# Ai_Cricket.net
KiCad netlist of a schematic drawn in EAGLE
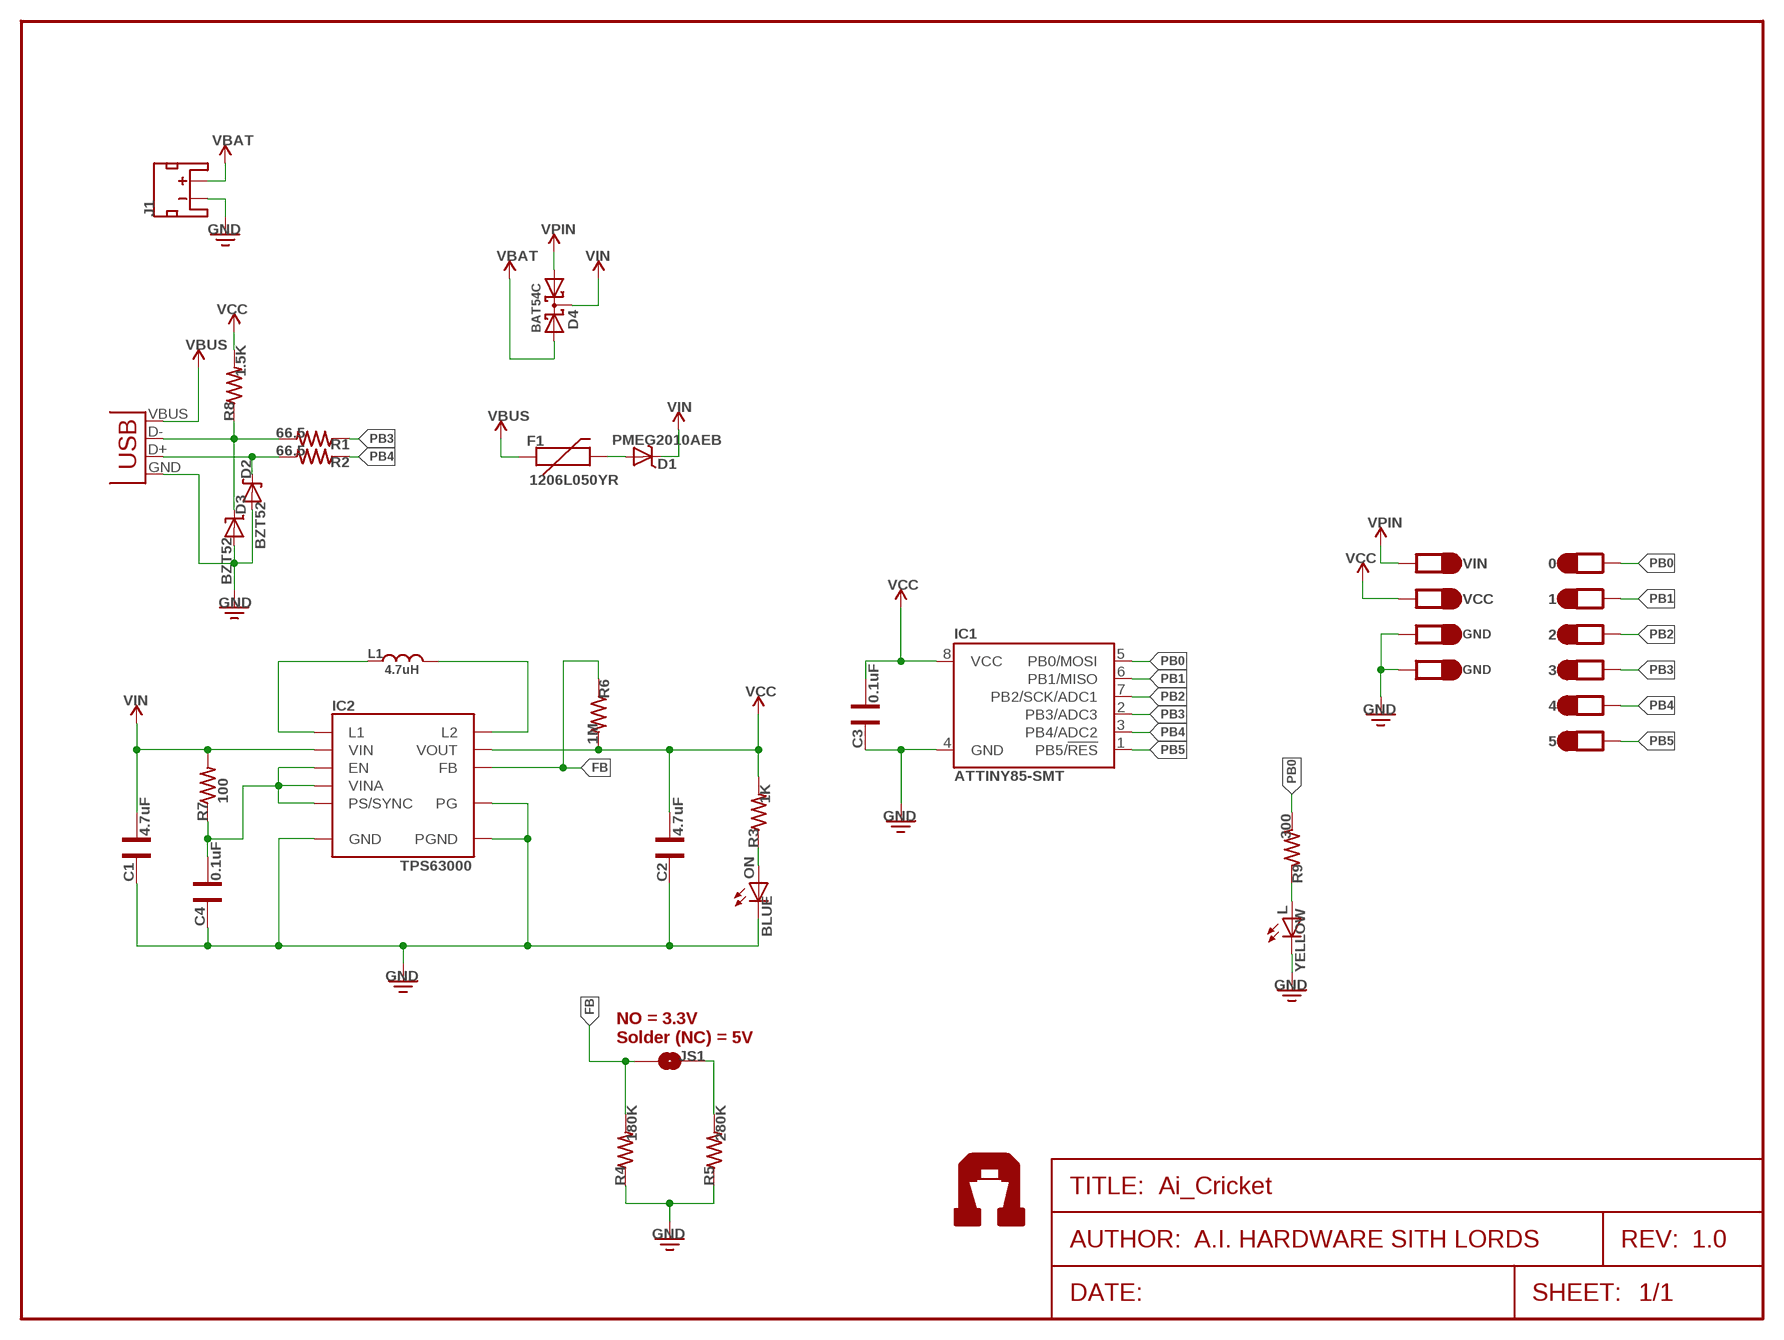
[diagram p0: schematic, sheet 1]

(export (version "E")
  (design (tool "Eeschema 10.0.6"))
  (components
    (comp (ref "0")
      (value "1X01-PETAL")
      (footprint "eagle-import:1X01-PETAL")
      (libsource (lib "eagle-import") (part "1X01-PETAL"))
    )
    (comp (ref "1")
      (value "1X01-PETAL")
      (footprint "eagle-import:1X01-PETAL")
      (libsource (lib "eagle-import") (part "1X01-PETAL"))
    )
    (comp (ref "2")
      (value "1X01-PETAL")
      (footprint "eagle-import:1X01-PETAL")
      (libsource (lib "eagle-import") (part "1X01-PETAL"))
    )
    (comp (ref "3")
      (value "1X01-PETAL")
      (footprint "eagle-import:1X01-PETAL")
      (libsource (lib "eagle-import") (part "1X01-PETAL"))
    )
    (comp (ref "4")
      (value "1X01-PETAL")
      (footprint "eagle-import:1X01-PETAL")
      (libsource (lib "eagle-import") (part "1X01-PETAL"))
    )
    (comp (ref "5")
      (value "1X01-PETAL")
      (footprint "eagle-import:1X01-PETAL")
      (libsource (lib "eagle-import") (part "1X01-PETAL"))
    )
    (comp (ref "C1")
      (value "4.7uF")
      (footprint "eagle-import:CAP-0402")
      (libsource (lib "eagle-import") (part "CAP0402"))
    )
    (comp (ref "C2")
      (value "4.7uF")
      (footprint "eagle-import:CAP-0402")
      (libsource (lib "eagle-import") (part "CAP0402"))
    )
    (comp (ref "C3")
      (value "0.1uF")
      (footprint "eagle-import:CAP-0402")
      (libsource (lib "eagle-import") (part "CAP0402"))
    )
    (comp (ref "C4")
      (value "0.1uF")
      (footprint "eagle-import:CAP-0402")
      (libsource (lib "eagle-import") (part "CAP0402"))
    )
    (comp (ref "D1")
      (value "PMEG2010AEB")
      (footprint "eagle-import:SOD-523")
      (libsource (lib "eagle-import") (part "DIODE-SCHOTTKYSOD-523"))
    )
    (comp (ref "D2")
      (value "BZT52")
      (footprint "eagle-import:SOD-323")
      (libsource (lib "eagle-import") (part "DIODE-ZENER-BZT52"))
    )
    (comp (ref "D3")
      (value "BZT52")
      (footprint "eagle-import:SOD-323")
      (libsource (lib "eagle-import") (part "DIODE-ZENER-BZT52"))
    )
    (comp (ref "D4")
      (value "BAT54C")
      (footprint "eagle-import:SOT-23")
      (libsource (lib "eagle-import") (part "BAT54C"))
    )
    (comp (ref "F1")
      (value "1206L050YR")
      (footprint "eagle-import:PTC-1206")
      (libsource (lib "eagle-import") (part "PTCSMD"))
    )
    (comp (ref "GND7")
      (value "1X01-PETAL")
      (footprint "eagle-import:1X01-PETAL")
      (libsource (lib "eagle-import") (part "1X01-PETAL"))
    )
    (comp (ref "GND8")
      (value "1X01-PETAL")
      (footprint "eagle-import:1X01-PETAL")
      (libsource (lib "eagle-import") (part "1X01-PETAL"))
    )
    (comp (ref "IC1")
      (value "ATTINY85-SMT")
      (footprint "eagle-import:S008-EIAJ")
      (libsource (lib "eagle-import") (part "ATTINY85-SMT"))
    )
    (comp (ref "IC2")
      (value "TPS63000")
      (footprint "eagle-import:10-VFDFN")
      (libsource (lib "eagle-import") (part "TPS63000"))
    )
    (comp (ref "J1")
      (value "JST-2-MALE")
      (footprint "eagle-import:JST-2-SMD")
      (libsource (lib "eagle-import") (part "JST-2-MALE"))
    )
    (comp (ref "JS1")
      (value "1X02-SJ-NO")
      (footprint "eagle-import:1X02-SJ-NO")
      (libsource (lib "eagle-import") (part "1X02-SJ-NO"))
    )
    (comp (ref "L")
      (value "YELLOW")
      (footprint "eagle-import:LED-0603")
      (libsource (lib "eagle-import") (part "LED0603"))
    )
    (comp (ref "L1")
      (value "4.7uH")
      (footprint "eagle-import:IND-0603")
      (libsource (lib "eagle-import") (part "IND0603"))
    )
    (comp (ref "ON")
      (value "BLUE")
      (footprint "eagle-import:LED-0603")
      (libsource (lib "eagle-import") (part "LED0603"))
    )
    (comp (ref "R1")
      (value "66.5")
      (footprint "eagle-import:RES-0402")
      (libsource (lib "eagle-import") (part "RES0402"))
    )
    (comp (ref "R2")
      (value "66.5")
      (footprint "eagle-import:RES-0402")
      (libsource (lib "eagle-import") (part "RES0402"))
    )
    (comp (ref "R3")
      (value "1K")
      (footprint "eagle-import:RES-0402")
      (libsource (lib "eagle-import") (part "RES0402"))
    )
    (comp (ref "R4")
      (value "180K")
      (footprint "eagle-import:RES-0402")
      (libsource (lib "eagle-import") (part "RES0402"))
    )
    (comp (ref "R5")
      (value "280K")
      (footprint "eagle-import:RES-0402")
      (libsource (lib "eagle-import") (part "RES0402"))
    )
    (comp (ref "R6")
      (value "1M")
      (footprint "eagle-import:RES-0402")
      (libsource (lib "eagle-import") (part "RES0402"))
    )
    (comp (ref "R7")
      (value "100")
      (footprint "eagle-import:RES-0402")
      (libsource (lib "eagle-import") (part "RES0402"))
    )
    (comp (ref "R8")
      (value "1.5K")
      (footprint "eagle-import:RES-0402")
      (libsource (lib "eagle-import") (part "RES0402"))
    )
    (comp (ref "R9")
      (value "300")
      (footprint "eagle-import:RES-0402")
      (libsource (lib "eagle-import") (part "RES0402"))
    )
    (comp (ref "U$14")
      (value "AI-LOGOXS")
      (footprint "eagle-import:AI-LOGO-XS")
      (libsource (lib "eagle-import") (part "AI-LOGOXS"))
    )
    (comp (ref "USB1")
      (value "USBMICROB-TH")
      (footprint "eagle-import:USB-MICROB-TH")
      (libsource (lib "eagle-import") (part "USBMICROB-TH"))
    )
    (comp (ref "VCC")
      (value "1X01-PETAL")
      (footprint "eagle-import:1X01-PETAL")
      (libsource (lib "eagle-import") (part "1X01-PETAL"))
    )
    (comp (ref "VIN")
      (value "1X01-PETAL")
      (footprint "eagle-import:1X01-PETAL")
      (libsource (lib "eagle-import") (part "1X01-PETAL"))
    )
  )
  (nets
    (net (code "1") (name "FB") (class "Default")
      (node (ref "IC2") (pin "10") (pinfunction "FB_10") (pintype "input"))
      (node (ref "JS1") (pin "1") (pinfunction "1_1") (pintype "passive"))
      (node (ref "R4") (pin "2") (pinfunction "2_2") (pintype "passive"))
      (node (ref "R6") (pin "1") (pinfunction "1_1") (pintype "passive"))
    )
    (net (code "2") (name "GND") (class "Default")
      (node (ref "C1") (pin "2") (pinfunction "2_2") (pintype "passive"))
      (node (ref "C2") (pin "2") (pinfunction "2_2") (pintype "passive"))
      (node (ref "C3") (pin "2") (pinfunction "2_2") (pintype "passive"))
      (node (ref "C4") (pin "2") (pinfunction "2_2") (pintype "passive"))
      (node (ref "D2") (pin "A") (pinfunction "A_A") (pintype "passive"))
      (node (ref "D3") (pin "A") (pinfunction "A_A") (pintype "passive"))
      (node (ref "GND7") (pin "1") (pinfunction "1_1") (pintype "bidirectional"))
      (node (ref "GND8") (pin "1") (pinfunction "1_1") (pintype "bidirectional"))
      (node (ref "IC1") (pin "4") (pinfunction "GND_4") (pintype "bidirectional"))
      (node (ref "IC2") (pin "3") (pinfunction "PGND_3") (pintype "power_in"))
      (node (ref "IC2") (pin "9") (pinfunction "GND_9") (pintype "power_in"))
      (node (ref "IC2") (pin "P$1") (pinfunction "PG_P$1") (pintype "power_in"))
      (node (ref "IC2") (pin "P$2") (pinfunction "PG_P$2") (pintype "power_in"))
      (node (ref "IC2") (pin "P$3") (pinfunction "PG_P$3") (pintype "power_in"))
      (node (ref "IC2") (pin "P$4") (pinfunction "PG_P$4") (pintype "power_in"))
      (node (ref "IC2") (pin "P$5") (pinfunction "PG_P$5") (pintype "power_in"))
      (node (ref "J1") (pin "2") (pinfunction "-_2") (pintype "power_in"))
      (node (ref "L") (pin "C") (pinfunction "C_C") (pintype "passive"))
      (node (ref "ON") (pin "C") (pinfunction "C_C") (pintype "passive"))
      (node (ref "R4") (pin "1") (pinfunction "1_1") (pintype "passive"))
      (node (ref "R5") (pin "1") (pinfunction "1_1") (pintype "passive"))
      (node (ref "USB1") (pin "GND") (pinfunction "GND_GND") (pintype "bidirectional"))
    )
    (net (code "3") (name "Net-(D1-PadA)") (class "Default")
      (node (ref "D1") (pin "A") (pinfunction "A_A") (pintype "passive"))
      (node (ref "F1") (pin "2") (pinfunction "2_2") (pintype "bidirectional"))
    )
    (net (code "4") (name "Net-(D2-PadC)") (class "Default")
      (node (ref "D2") (pin "C") (pinfunction "C_C") (pintype "passive"))
      (node (ref "R2") (pin "2") (pinfunction "2_2") (pintype "passive"))
      (node (ref "USB1") (pin "D+") (pinfunction "D+_D+") (pintype "bidirectional"))
    )
    (net (code "5") (name "Net-(D3-PadC)") (class "Default")
      (node (ref "D3") (pin "C") (pinfunction "C_C") (pintype "passive"))
      (node (ref "R1") (pin "2") (pinfunction "2_2") (pintype "passive"))
      (node (ref "R8") (pin "1") (pinfunction "1_1") (pintype "passive"))
      (node (ref "USB1") (pin "D-") (pinfunction "D-_D-") (pintype "bidirectional"))
    )
    (net (code "6") (name "Net-(IC2-EN)") (class "Default")
      (node (ref "C4") (pin "1") (pinfunction "1_1") (pintype "passive"))
      (node (ref "IC2") (pin "6") (pinfunction "EN_6") (pintype "bidirectional"))
      (node (ref "IC2") (pin "7") (pinfunction "PS/SYNC_7") (pintype "input"))
      (node (ref "IC2") (pin "8") (pinfunction "VINA_8") (pintype "power_in"))
      (node (ref "R7") (pin "1") (pinfunction "1_1") (pintype "passive"))
    )
    (net (code "7") (name "Net-(IC2-L1)") (class "Default")
      (node (ref "IC2") (pin "4") (pinfunction "L1_4") (pintype "passive"))
      (node (ref "L1") (pin "2") (pinfunction "2_2") (pintype "passive"))
    )
    (net (code "8") (name "Net-(IC2-L2)") (class "Default")
      (node (ref "IC2") (pin "2") (pinfunction "L2_2") (pintype "passive"))
      (node (ref "L1") (pin "1") (pinfunction "1_1") (pintype "passive"))
    )
    (net (code "9") (name "Net-(JS1-Pad2)") (class "Default")
      (node (ref "JS1") (pin "2") (pinfunction "2_2") (pintype "passive"))
      (node (ref "R5") (pin "2") (pinfunction "2_2") (pintype "passive"))
    )
    (net (code "10") (name "Net-(L-PadA)") (class "Default")
      (node (ref "L") (pin "A") (pinfunction "A_A") (pintype "passive"))
      (node (ref "R9") (pin "1") (pinfunction "1_1") (pintype "passive"))
    )
    (net (code "11") (name "Net-(ON-PadA)") (class "Default")
      (node (ref "ON") (pin "A") (pinfunction "A_A") (pintype "passive"))
      (node (ref "R3") (pin "1") (pinfunction "1_1") (pintype "passive"))
    )
    (net (code "12") (name "PB0") (class "Default")
      (node (ref "0") (pin "1") (pinfunction "1_1") (pintype "bidirectional"))
      (node (ref "IC1") (pin "5") (pinfunction "PB0/MOSI_5") (pintype "bidirectional"))
      (node (ref "R9") (pin "2") (pinfunction "2_2") (pintype "passive"))
    )
    (net (code "13") (name "PB1") (class "Default")
      (node (ref "1") (pin "1") (pinfunction "1_1") (pintype "bidirectional"))
      (node (ref "IC1") (pin "6") (pinfunction "PB1/MISO_6") (pintype "bidirectional"))
    )
    (net (code "14") (name "PB2") (class "Default")
      (node (ref "2") (pin "1") (pinfunction "1_1") (pintype "bidirectional"))
      (node (ref "IC1") (pin "7") (pinfunction "PB2/SCK/ADC1_7") (pintype "bidirectional"))
    )
    (net (code "15") (name "PB3") (class "Default")
      (node (ref "3") (pin "1") (pinfunction "1_1") (pintype "bidirectional"))
      (node (ref "IC1") (pin "2") (pinfunction "PB3/ADC3_2") (pintype "bidirectional"))
      (node (ref "R1") (pin "1") (pinfunction "1_1") (pintype "passive"))
    )
    (net (code "16") (name "PB4") (class "Default")
      (node (ref "4") (pin "1") (pinfunction "1_1") (pintype "bidirectional"))
      (node (ref "IC1") (pin "3") (pinfunction "PB4/ADC2_3") (pintype "bidirectional"))
      (node (ref "R2") (pin "1") (pinfunction "1_1") (pintype "passive"))
    )
    (net (code "17") (name "PB5") (class "Default")
      (node (ref "5") (pin "1") (pinfunction "1_1") (pintype "bidirectional"))
      (node (ref "IC1") (pin "1") (pinfunction "PB5/~{RES}_1") (pintype "bidirectional"))
    )
    (net (code "18") (name "VBAT") (class "Default")
      (node (ref "D4") (pin "2") (pinfunction "A2_2") (pintype "passive"))
      (node (ref "J1") (pin "1") (pinfunction "+_1") (pintype "power_in"))
    )
    (net (code "19") (name "VBUS") (class "Default")
      (node (ref "F1") (pin "1") (pinfunction "1_1") (pintype "bidirectional"))
      (node (ref "USB1") (pin "VBUS") (pinfunction "VBUS_VBUS") (pintype "bidirectional"))
    )
    (net (code "20") (name "VCC") (class "Default")
      (node (ref "C2") (pin "1") (pinfunction "1_1") (pintype "passive"))
      (node (ref "C3") (pin "1") (pinfunction "1_1") (pintype "passive"))
      (node (ref "IC1") (pin "8") (pinfunction "VCC_8") (pintype "bidirectional"))
      (node (ref "IC2") (pin "1") (pinfunction "VOUT_1") (pintype "power_in"))
      (node (ref "R3") (pin "2") (pinfunction "2_2") (pintype "passive"))
      (node (ref "R6") (pin "2") (pinfunction "2_2") (pintype "passive"))
      (node (ref "R8") (pin "2") (pinfunction "2_2") (pintype "passive"))
      (node (ref "VCC") (pin "1") (pinfunction "1_1") (pintype "bidirectional"))
    )
    (net (code "21") (name "VIN") (class "Default")
      (node (ref "C1") (pin "1") (pinfunction "1_1") (pintype "passive"))
      (node (ref "D1") (pin "C") (pinfunction "C_C") (pintype "passive"))
      (node (ref "D4") (pin "3") (pinfunction "CC_3") (pintype "passive"))
      (node (ref "IC2") (pin "5") (pinfunction "VIN_5") (pintype "power_in"))
      (node (ref "R7") (pin "2") (pinfunction "2_2") (pintype "passive"))
    )
    (net (code "22") (name "VPIN") (class "Default")
      (node (ref "D4") (pin "1") (pinfunction "A1_1") (pintype "passive"))
      (node (ref "VIN") (pin "1") (pinfunction "1_1") (pintype "bidirectional"))
    )
  )
)
